# LM399_Reference.net
KiCad netlist of a schematic drawn in Altium Designer
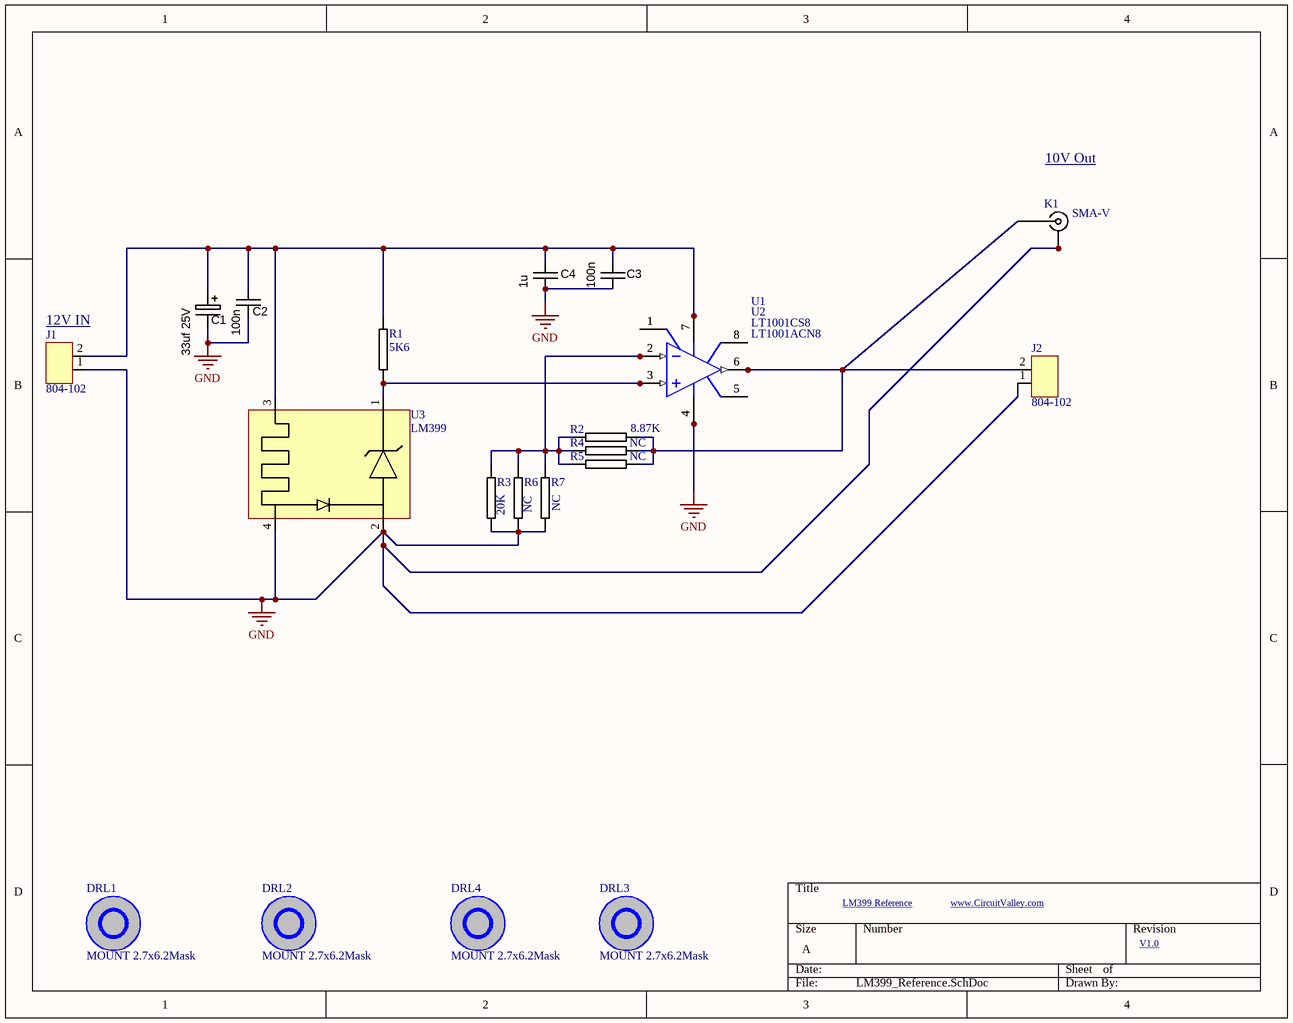
[diagram p0: LM399_Reference.SchDoc]

(export (version "E")
  (design (tool "Eeschema 10.0.6"))
  (components
    (comp (ref "C1")
      (value "33uf 25V")
      (footprint "CAPMP7343X310N")
      (description "Capacitor SMD Tant 330uF 20% 6V3 2917")
      (fields
        (field (name "TOLERANCE") "±20%")
        (field (name "MANUFACTURER PART NUMBER") "T520D337M006ATE015")
      )
      (libsource (lib "PBL - Capacitors") (part "CAPT_330u_2917_6V3"))
    )
    (comp (ref "C2")
      (value "100n")
      (footprint "CAPC1608N")
      (description "Capacitor SMD Cer 10pF 5% 50V NP0 0603")
      (fields (field (name "TOLERANCE") "±5%") (field (name "PART") "C0603X104K5RAC"))
      (libsource (lib "PBL - Capacitors") (part "CAPC_10p_0603_NP0_1%_50V"))
    )
    (comp (ref "C3")
      (value "100n")
      (footprint "CAPC1608N")
      (description "Capacitor SMD Cer 10pF 5% 50V NP0 0603")
      (fields (field (name "PART") "C0603X104K5RAC"))
      (libsource (lib "PBL - Capacitors") (part "CAPC_10p_0603_NP0_1%_50V"))
    )
    (comp (ref "C4")
      (value "1u")
      (footprint "CAPC1608N")
      (description "Capacitor SMD Cer 10pF 5% 50V NP0 0603")
      (fields (field (name "TOLERANCE") "±5%") (field (name "PART") "C0603X104K5RAC"))
      (libsource (lib "PBL - Capacitors") (part "CAPC_10p_0603_NP0_1%_50V"))
    )
    (comp (ref "DRL1")
      (value "MOUNT 2.7x6.2Mask")
      (footprint "NO_COPPER_NOMASK_2m75_6m2")
      (libsource (lib "mounting_hole") (part "DRILL_2.7x6.2Mask_NOCOPPER"))
    )
    (comp (ref "DRL2")
      (value "MOUNT 2.7x6.2Mask")
      (footprint "NO_COPPER_NOMASK_2m75_6m2")
      (libsource (lib "mounting_hole") (part "DRILL_2.7x6.2Mask_NOCOPPER"))
    )
    (comp (ref "DRL3")
      (value "MOUNT 2.7x6.2Mask")
      (footprint "NO_COPPER_NOMASK_2m75_6m2")
      (libsource (lib "mounting_hole") (part "DRILL_2.7x6.2Mask_NOCOPPER"))
    )
    (comp (ref "DRL4")
      (value "MOUNT 2.7x6.2Mask")
      (footprint "NO_COPPER_NOMASK_2m75_6m2")
      (libsource (lib "mounting_hole") (part "DRILL_2.7x6.2Mask_NOCOPPER"))
    )
    (comp (ref "J1") (value "804-102") (footprint "804-102") (libsource (lib "cvlib") (part "804-102")))
    (comp (ref "J2") (value "804-102") (footprint "804-102") (libsource (lib "") (part "804-102_1")))
    (comp (ref "K1")
      (value "SMA-V")
      (footprint "SMA-V")
      (description "SMA THREADED RF CONNECTOR VERTICAL")
      (libsource (lib "Generic") (part "SMA-V"))
    )
    (comp (ref "R1")
      (value "5K6")
      (footprint "0603R-GENERIC")
      (description "GENERIC RESISTOR 0603")
      (fields (field (name "PART") "RMCF0603JT7K50"))
      (libsource (lib "Generic") (part "0603R-7K5"))
    )
    (comp (ref "R2")
      (value "8.87K")
      (footprint "0603R-TBD")
      (description "RESISTOR 0603 VALUE TO BE DETERMINED")
      (fields (field (name "PART") "RN73C1J8K87BTG"))
      (libsource (lib "Generic") (part "0603R-TBD"))
    )
    (comp (ref "R3")
      (value "20K")
      (footprint "0603R-GENERIC")
      (description "GENERIC RESISTOR 0603")
      (fields (field (name "PART") "ERA-3ARW203V"))
      (libsource (lib "Generic") (part "0603R-20K"))
    )
    (comp (ref "R4")
      (value "NC")
      (footprint "0603R-TBD")
      (description "RESISTOR 0603 VALUE TO BE DETERMINED")
      (fields (field (name "PART") "RN73C1J8K87BTG"))
      (libsource (lib "Generic") (part "0603R-TBD"))
    )
    (comp (ref "R5")
      (value "NC")
      (footprint "0603R-TBD")
      (description "RESISTOR 0603 VALUE TO BE DETERMINED")
      (fields (field (name "PART") "RN73C1J8K87BTG"))
      (libsource (lib "Generic") (part "0603R-TBD"))
    )
    (comp (ref "R6")
      (value "NC")
      (footprint "0603R-GENERIC")
      (description "GENERIC RESISTOR 0603")
      (fields (field (name "PART") "ERA-3ARW203V"))
      (libsource (lib "Generic") (part "0603R-20K"))
    )
    (comp (ref "R7")
      (value "NC")
      (footprint "0603R-GENERIC")
      (description "GENERIC RESISTOR 0603")
      (fields (field (name "PART") "ERA-3ARW203V"))
      (libsource (lib "Generic") (part "0603R-20K"))
    )
    (comp (ref "U1")
      (value "LT1001CS8")
      (footprint "S8_N")
      (description "General Purpose, High Precision Op Amp")
      (fields (field (name "PART") "LT100ACN8"))
      (libsource (lib "LT Operational Amplifier") (part "LT1001CS8"))
    )
    (comp (ref "U2")
      (value "LT1001ACN8")
      (footprint "N8")
      (description "General Purpose, High Precision Op Amp")
      (fields (field (name "PUBLISHER") "Altium Limited"))
      (libsource (lib "LT Operational Amplifier") (part "LT1001ACN8"))
    )
    (comp (ref "U3") (value "LM399") (footprint "TO-46") (libsource (lib "cvlib") (part "LM399")))
  )
  (nets
    (net (code "1") (name "GND") (class "Default")
      (node (ref "C1") (pin "2") (pintype "passive"))
      (node (ref "C2") (pin "1") (pintype "passive"))
      (node (ref "C3") (pin "1") (pintype "passive"))
      (node (ref "C4") (pin "1") (pintype "passive"))
      (node (ref "J1") (pin "1") (pinfunction "PW_1") (pintype "passive"))
      (node (ref "J2") (pin "1") (pinfunction "PW_1") (pintype "passive"))
      (node (ref "K1") (pin "2") (pinfunction "2_2") (pintype "passive"))
      (node (ref "K1") (pin "3") (pinfunction "3_3") (pintype "passive"))
      (node (ref "K1") (pin "4") (pinfunction "4_4") (pintype "passive"))
      (node (ref "K1") (pin "5") (pinfunction "5_5") (pintype "passive"))
      (node (ref "R3") (pin "1") (pintype "passive"))
      (node (ref "R6") (pin "1") (pintype "passive"))
      (node (ref "R7") (pin "1") (pintype "passive"))
      (node (ref "U1") (pin "4") (pinfunction "V-_4") (pintype "power_in"))
      (node (ref "U2") (pin "4") (pinfunction "V-_4") (pintype "power_in"))
      (node (ref "U3") (pin "2") (pinfunction "D2_2") (pintype "passive"))
      (node (ref "U3") (pin "4") (pinfunction "H2_4") (pintype "passive"))
    )
    (net (code "2") (name "Net-(U1-IN+)") (class "Default")
      (node (ref "R1") (pin "2") (pintype "passive"))
      (node (ref "U1") (pin "3") (pinfunction "IN+_3") (pintype "input"))
      (node (ref "U2") (pin "3") (pinfunction "IN+_3") (pintype "input"))
      (node (ref "U3") (pin "1") (pinfunction "D1_1") (pintype "passive"))
    )
    (net (code "3") (name "Net-(U1-IN-)") (class "Default")
      (node (ref "R2") (pin "1") (pintype "passive"))
      (node (ref "R3") (pin "2") (pintype "passive"))
      (node (ref "R4") (pin "1") (pintype "passive"))
      (node (ref "R5") (pin "1") (pintype "passive"))
      (node (ref "R6") (pin "2") (pintype "passive"))
      (node (ref "R7") (pin "2") (pintype "passive"))
      (node (ref "U1") (pin "2") (pinfunction "IN-_2") (pintype "input"))
      (node (ref "U2") (pin "2") (pinfunction "IN-_2") (pintype "input"))
    )
    (net (code "4") (name "Net-(U1-NC)") (class "Default")
      (node (ref "U1") (pin "5") (pinfunction "NC_5") (pintype "passive"))
      (node (ref "U2") (pin "5") (pinfunction "NC_5") (pintype "passive"))
    )
    (net (code "5") (name "Net-(U1-OUT)") (class "Default")
      (node (ref "J2") (pin "2") (pinfunction "PW_2") (pintype "passive"))
      (node (ref "K1") (pin "1") (pinfunction "1_1") (pintype "passive"))
      (node (ref "R2") (pin "2") (pintype "passive"))
      (node (ref "R4") (pin "2") (pintype "passive"))
      (node (ref "R5") (pin "2") (pintype "passive"))
      (node (ref "U1") (pin "6") (pinfunction "OUT_6") (pintype "output"))
      (node (ref "U2") (pin "6") (pinfunction "OUT_6") (pintype "output"))
    )
    (net (code "6") (name "Net-(U1-V+)") (class "Default")
      (node (ref "C1") (pin "1") (pintype "passive"))
      (node (ref "C2") (pin "2") (pintype "passive"))
      (node (ref "C3") (pin "2") (pintype "passive"))
      (node (ref "C4") (pin "2") (pintype "passive"))
      (node (ref "J1") (pin "2") (pinfunction "PW_2") (pintype "passive"))
      (node (ref "R1") (pin "1") (pintype "passive"))
      (node (ref "U1") (pin "7") (pinfunction "V+_7") (pintype "power_in"))
      (node (ref "U2") (pin "7") (pinfunction "V+_7") (pintype "power_in"))
      (node (ref "U3") (pin "3") (pinfunction "H1_3") (pintype "passive"))
    )
    (net (code "7") (name "Net-(U1-VOSTRIM-Pad1)") (class "Default")
      (node (ref "U1") (pin "1") (pinfunction "VOSTRIM_1") (pintype "passive"))
      (node (ref "U2") (pin "1") (pinfunction "VOSTRIM_1") (pintype "passive"))
    )
    (net (code "8") (name "Net-(U1-VOSTRIM-Pad8)") (class "Default")
      (node (ref "U1") (pin "8") (pinfunction "VOSTRIM_8") (pintype "passive"))
      (node (ref "U2") (pin "8") (pinfunction "VOSTRIM_8") (pintype "passive"))
    )
  )
)
